# 08_INPUTCAPTURE_ENCODER.net
KiCad netlist of a schematic drawn in Altium Designer
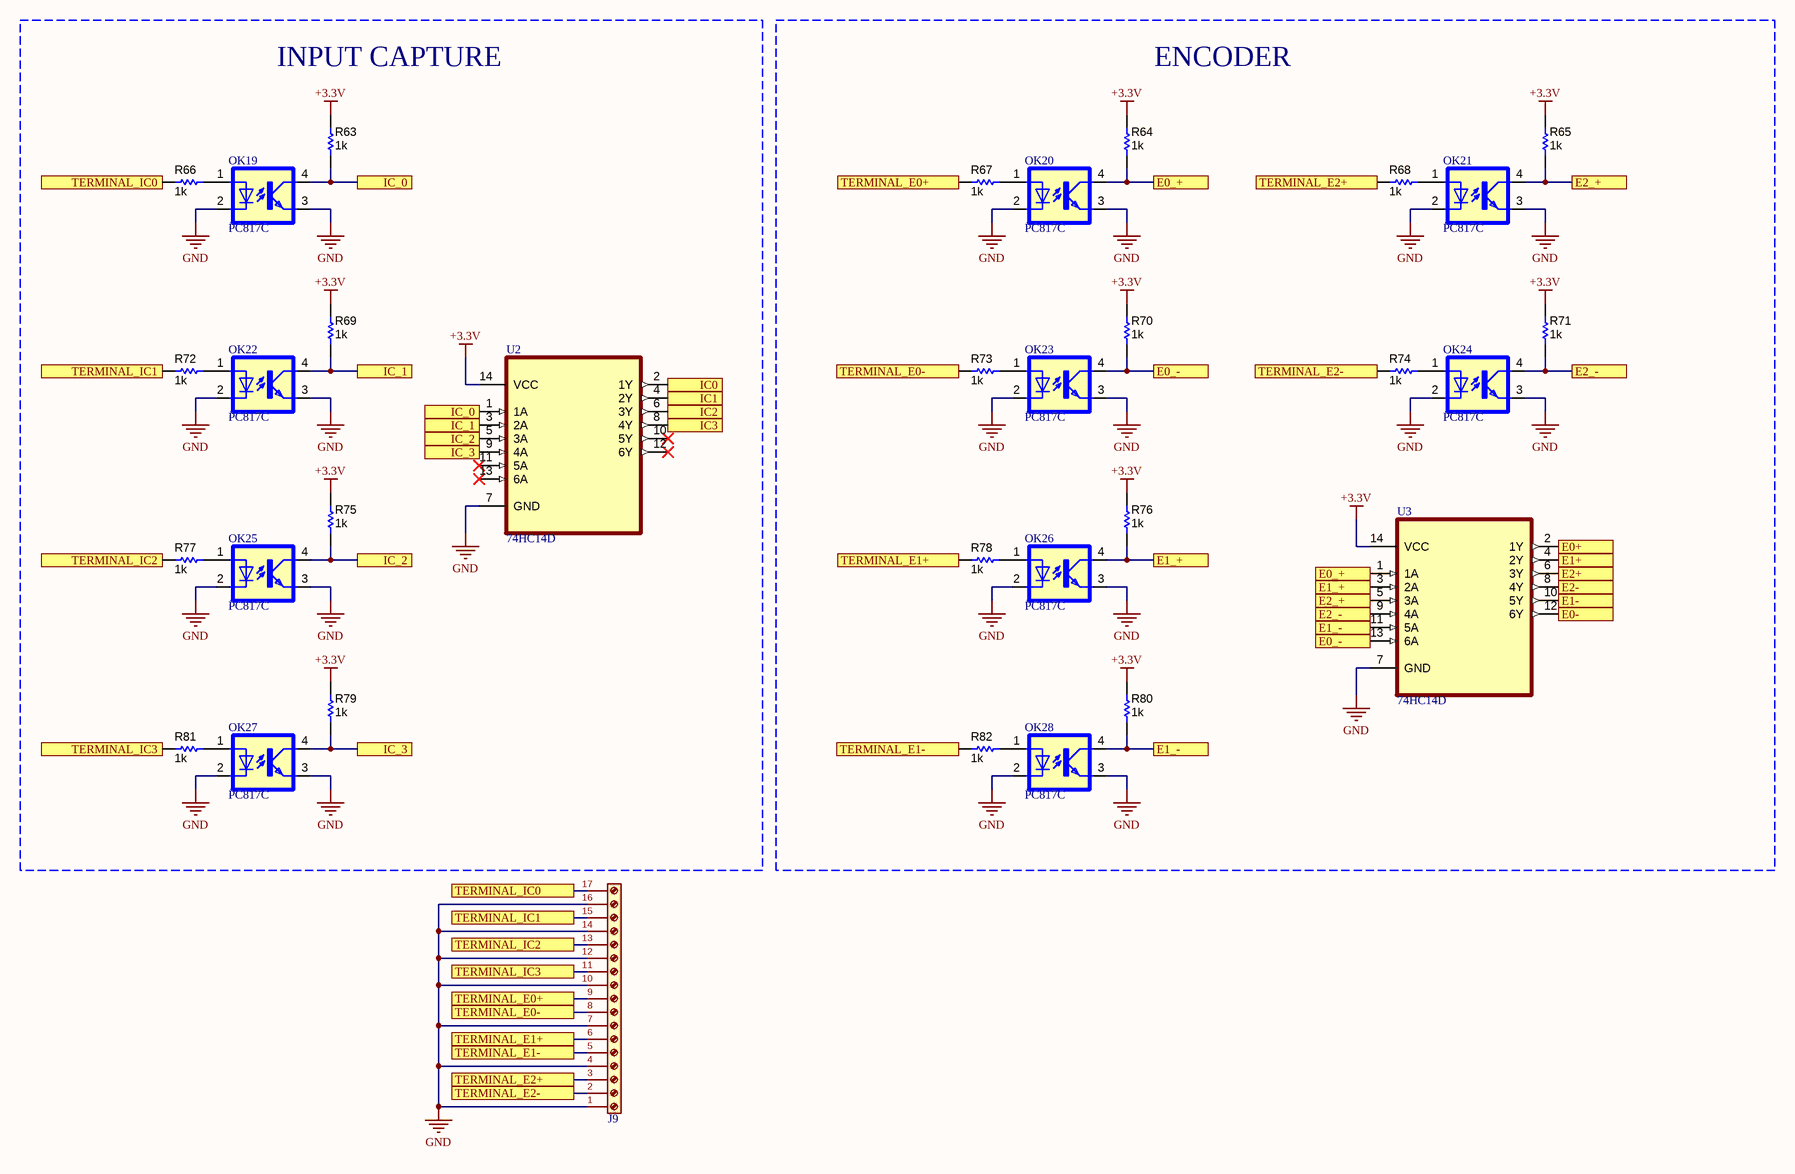
[diagram p0: 08_INPUTCAPTURE_ENCODER.SchDoc]

(export (version "E")
  (design (tool "Eeschema 10.0.6"))
  (components
    (comp (ref "J9")
      (value "Terminal_01x17_P5.00")
      (footprint "TerminalBlock_Phoenix_PT-1,5-17-5.0-H_1x17_P5.00mm_Horizontal")
      (libsource (lib "PROC051C_AWR1843BOOST_RevC") (part "Terminal_01x17_P5.00"))
    )
    (comp (ref "OK19")
      (value "PC817C")
      (footprint "SOP254P975X460-4N")
      (description "RF Mixer IC Cellular, DCS, PCS, W-CDMA, WLAN Up Converter 50MHz ~ 400MHz 6-SuperMiniMold")
      (fields (field (name "MF") "Renesas Electronics America Inc") (field (name "MP") "PC817"))
      (libsource (lib "PROC051C_AWR1843BOOST_RevC") (part "PC817C"))
    )
    (comp (ref "OK20")
      (value "PC817C")
      (footprint "SOP254P975X460-4N")
      (description "RF Mixer IC Cellular, DCS, PCS, W-CDMA, WLAN Up Converter 50MHz ~ 400MHz 6-SuperMiniMold")
      (fields (field (name "MF") "Renesas Electronics America Inc") (field (name "MP") "PC817"))
      (libsource (lib "PROC051C_AWR1843BOOST_RevC") (part "PC817C"))
    )
    (comp (ref "OK21")
      (value "PC817C")
      (footprint "SOP254P975X460-4N")
      (description "RF Mixer IC Cellular, DCS, PCS, W-CDMA, WLAN Up Converter 50MHz ~ 400MHz 6-SuperMiniMold")
      (fields (field (name "MF") "Renesas Electronics America Inc") (field (name "MP") "PC817"))
      (libsource (lib "PROC051C_AWR1843BOOST_RevC") (part "PC817C"))
    )
    (comp (ref "OK22")
      (value "PC817C")
      (footprint "SOP254P975X460-4N")
      (description "RF Mixer IC Cellular, DCS, PCS, W-CDMA, WLAN Up Converter 50MHz ~ 400MHz 6-SuperMiniMold")
      (fields (field (name "MF") "Renesas Electronics America Inc") (field (name "MP") "PC817"))
      (libsource (lib "PROC051C_AWR1843BOOST_RevC") (part "PC817C"))
    )
    (comp (ref "OK23")
      (value "PC817C")
      (footprint "SOP254P975X460-4N")
      (description "RF Mixer IC Cellular, DCS, PCS, W-CDMA, WLAN Up Converter 50MHz ~ 400MHz 6-SuperMiniMold")
      (fields (field (name "MF") "Renesas Electronics America Inc") (field (name "MP") "PC817"))
      (libsource (lib "PROC051C_AWR1843BOOST_RevC") (part "PC817C"))
    )
    (comp (ref "OK24")
      (value "PC817C")
      (footprint "SOP254P975X460-4N")
      (description "RF Mixer IC Cellular, DCS, PCS, W-CDMA, WLAN Up Converter 50MHz ~ 400MHz 6-SuperMiniMold")
      (fields (field (name "MF") "Renesas Electronics America Inc") (field (name "MP") "PC817"))
      (libsource (lib "PROC051C_AWR1843BOOST_RevC") (part "PC817C"))
    )
    (comp (ref "OK25")
      (value "PC817C")
      (footprint "SOP254P975X460-4N")
      (description "RF Mixer IC Cellular, DCS, PCS, W-CDMA, WLAN Up Converter 50MHz ~ 400MHz 6-SuperMiniMold")
      (fields (field (name "MF") "Renesas Electronics America Inc") (field (name "MP") "PC817"))
      (libsource (lib "PROC051C_AWR1843BOOST_RevC") (part "PC817C"))
    )
    (comp (ref "OK26")
      (value "PC817C")
      (footprint "SOP254P975X460-4N")
      (description "RF Mixer IC Cellular, DCS, PCS, W-CDMA, WLAN Up Converter 50MHz ~ 400MHz 6-SuperMiniMold")
      (fields (field (name "MF") "Renesas Electronics America Inc") (field (name "MP") "PC817"))
      (libsource (lib "PROC051C_AWR1843BOOST_RevC") (part "PC817C"))
    )
    (comp (ref "OK27")
      (value "PC817C")
      (footprint "SOP254P975X460-4N")
      (description "RF Mixer IC Cellular, DCS, PCS, W-CDMA, WLAN Up Converter 50MHz ~ 400MHz 6-SuperMiniMold")
      (fields (field (name "MF") "Renesas Electronics America Inc") (field (name "MP") "PC817"))
      (libsource (lib "PROC051C_AWR1843BOOST_RevC") (part "PC817C"))
    )
    (comp (ref "OK28")
      (value "PC817C")
      (footprint "SOP254P975X460-4N")
      (description "RF Mixer IC Cellular, DCS, PCS, W-CDMA, WLAN Up Converter 50MHz ~ 400MHz 6-SuperMiniMold")
      (fields (field (name "MF") "Renesas Electronics America Inc") (field (name "MP") "PC817"))
      (libsource (lib "PROC051C_AWR1843BOOST_RevC") (part "PC817C"))
    )
    (comp (ref "R63")
      (value "MCT06030Z0000ZP500")
      (footprint "0603")
      (description "RES, 0, 5%, 0.125 W, 0603")
      (fields
        (field (name "MANUFACTURER") "Vishay/Beyschlag")
        (field (name "VALUEDISPLAYED") "1k")
        (field (name "PUBLISHER") "Texas Instruments")
      )
      (libsource (lib "PROC051C_AWR1843BOOST_RevC") (part "RES 0R 0603"))
    )
    (comp (ref "R64")
      (value "MCT06030Z0000ZP500")
      (footprint "0603")
      (description "RES, 0, 5%, 0.125 W, 0603")
      (fields
        (field (name "MANUFACTURER") "Vishay/Beyschlag")
        (field (name "VALUEDISPLAYED") "1k")
        (field (name "PUBLISHER") "Texas Instruments")
      )
      (libsource (lib "PROC051C_AWR1843BOOST_RevC") (part "RES 0R 0603"))
    )
    (comp (ref "R65")
      (value "MCT06030Z0000ZP500")
      (footprint "0603")
      (description "RES, 0, 5%, 0.125 W, 0603")
      (fields
        (field (name "MANUFACTURER") "Vishay/Beyschlag")
        (field (name "VALUEDISPLAYED") "1k")
        (field (name "PUBLISHER") "Texas Instruments")
      )
      (libsource (lib "PROC051C_AWR1843BOOST_RevC") (part "RES 0R 0603"))
    )
    (comp (ref "R66")
      (value "MCT06030Z0000ZP500")
      (footprint "0603")
      (description "RES, 0, 5%, 0.125 W, 0603")
      (fields
        (field (name "MANUFACTURER") "Vishay/Beyschlag")
        (field (name "VALUEDISPLAYED") "1k")
        (field (name "PUBLISHER") "Texas Instruments")
      )
      (libsource (lib "PROC051C_AWR1843BOOST_RevC") (part "RES 0R 0603"))
    )
    (comp (ref "R67")
      (value "MCT06030Z0000ZP500")
      (footprint "0603")
      (description "RES, 0, 5%, 0.125 W, 0603")
      (fields
        (field (name "MANUFACTURER") "Vishay/Beyschlag")
        (field (name "VALUEDISPLAYED") "1k")
        (field (name "PUBLISHER") "Texas Instruments")
      )
      (libsource (lib "PROC051C_AWR1843BOOST_RevC") (part "RES 0R 0603"))
    )
    (comp (ref "R68")
      (value "MCT06030Z0000ZP500")
      (footprint "0603")
      (description "RES, 0, 5%, 0.125 W, 0603")
      (fields
        (field (name "MANUFACTURER") "Vishay/Beyschlag")
        (field (name "VALUEDISPLAYED") "1k")
        (field (name "PUBLISHER") "Texas Instruments")
      )
      (libsource (lib "PROC051C_AWR1843BOOST_RevC") (part "RES 0R 0603"))
    )
    (comp (ref "R69")
      (value "MCT06030Z0000ZP500")
      (footprint "0603")
      (description "RES, 0, 5%, 0.125 W, 0603")
      (fields
        (field (name "MANUFACTURER") "Vishay/Beyschlag")
        (field (name "VALUEDISPLAYED") "1k")
        (field (name "PUBLISHER") "Texas Instruments")
      )
      (libsource (lib "PROC051C_AWR1843BOOST_RevC") (part "RES 0R 0603"))
    )
    (comp (ref "R70")
      (value "MCT06030Z0000ZP500")
      (footprint "0603")
      (description "RES, 0, 5%, 0.125 W, 0603")
      (fields
        (field (name "MANUFACTURER") "Vishay/Beyschlag")
        (field (name "VALUEDISPLAYED") "1k")
        (field (name "PUBLISHER") "Texas Instruments")
      )
      (libsource (lib "PROC051C_AWR1843BOOST_RevC") (part "RES 0R 0603"))
    )
    (comp (ref "R71")
      (value "MCT06030Z0000ZP500")
      (footprint "0603")
      (description "RES, 0, 5%, 0.125 W, 0603")
      (fields
        (field (name "MANUFACTURER") "Vishay/Beyschlag")
        (field (name "VALUEDISPLAYED") "1k")
        (field (name "PUBLISHER") "Texas Instruments")
      )
      (libsource (lib "PROC051C_AWR1843BOOST_RevC") (part "RES 0R 0603"))
    )
    (comp (ref "R72")
      (value "MCT06030Z0000ZP500")
      (footprint "0603")
      (description "RES, 0, 5%, 0.125 W, 0603")
      (fields
        (field (name "MANUFACTURER") "Vishay/Beyschlag")
        (field (name "VALUEDISPLAYED") "1k")
        (field (name "PUBLISHER") "Texas Instruments")
      )
      (libsource (lib "PROC051C_AWR1843BOOST_RevC") (part "RES 0R 0603"))
    )
    (comp (ref "R73")
      (value "MCT06030Z0000ZP500")
      (footprint "0603")
      (description "RES, 0, 5%, 0.125 W, 0603")
      (fields
        (field (name "MANUFACTURER") "Vishay/Beyschlag")
        (field (name "VALUEDISPLAYED") "1k")
        (field (name "PUBLISHER") "Texas Instruments")
      )
      (libsource (lib "PROC051C_AWR1843BOOST_RevC") (part "RES 0R 0603"))
    )
    (comp (ref "R74")
      (value "MCT06030Z0000ZP500")
      (footprint "0603")
      (description "RES, 0, 5%, 0.125 W, 0603")
      (fields
        (field (name "MANUFACTURER") "Vishay/Beyschlag")
        (field (name "VALUEDISPLAYED") "1k")
        (field (name "PUBLISHER") "Texas Instruments")
      )
      (libsource (lib "PROC051C_AWR1843BOOST_RevC") (part "RES 0R 0603"))
    )
    (comp (ref "R75")
      (value "MCT06030Z0000ZP500")
      (footprint "0603")
      (description "RES, 0, 5%, 0.125 W, 0603")
      (fields
        (field (name "MANUFACTURER") "Vishay/Beyschlag")
        (field (name "VALUEDISPLAYED") "1k")
        (field (name "PUBLISHER") "Texas Instruments")
      )
      (libsource (lib "PROC051C_AWR1843BOOST_RevC") (part "RES 0R 0603"))
    )
    (comp (ref "R76")
      (value "MCT06030Z0000ZP500")
      (footprint "0603")
      (description "RES, 0, 5%, 0.125 W, 0603")
      (fields
        (field (name "MANUFACTURER") "Vishay/Beyschlag")
        (field (name "VALUEDISPLAYED") "1k")
        (field (name "PUBLISHER") "Texas Instruments")
      )
      (libsource (lib "PROC051C_AWR1843BOOST_RevC") (part "RES 0R 0603"))
    )
    (comp (ref "R77")
      (value "MCT06030Z0000ZP500")
      (footprint "0603")
      (description "RES, 0, 5%, 0.125 W, 0603")
      (fields
        (field (name "MANUFACTURER") "Vishay/Beyschlag")
        (field (name "VALUEDISPLAYED") "1k")
        (field (name "PUBLISHER") "Texas Instruments")
      )
      (libsource (lib "PROC051C_AWR1843BOOST_RevC") (part "RES 0R 0603"))
    )
    (comp (ref "R78")
      (value "MCT06030Z0000ZP500")
      (footprint "0603")
      (description "RES, 0, 5%, 0.125 W, 0603")
      (fields
        (field (name "MANUFACTURER") "Vishay/Beyschlag")
        (field (name "VALUEDISPLAYED") "1k")
        (field (name "PUBLISHER") "Texas Instruments")
      )
      (libsource (lib "PROC051C_AWR1843BOOST_RevC") (part "RES 0R 0603"))
    )
    (comp (ref "R79")
      (value "MCT06030Z0000ZP500")
      (footprint "0603")
      (description "RES, 0, 5%, 0.125 W, 0603")
      (fields
        (field (name "MANUFACTURER") "Vishay/Beyschlag")
        (field (name "VALUEDISPLAYED") "1k")
        (field (name "PUBLISHER") "Texas Instruments")
      )
      (libsource (lib "PROC051C_AWR1843BOOST_RevC") (part "RES 0R 0603"))
    )
    (comp (ref "R80")
      (value "MCT06030Z0000ZP500")
      (footprint "0603")
      (description "RES, 0, 5%, 0.125 W, 0603")
      (fields
        (field (name "MANUFACTURER") "Vishay/Beyschlag")
        (field (name "VALUEDISPLAYED") "1k")
        (field (name "PUBLISHER") "Texas Instruments")
      )
      (libsource (lib "PROC051C_AWR1843BOOST_RevC") (part "RES 0R 0603"))
    )
    (comp (ref "R81")
      (value "MCT06030Z0000ZP500")
      (footprint "0603")
      (description "RES, 0, 5%, 0.125 W, 0603")
      (fields
        (field (name "MANUFACTURER") "Vishay/Beyschlag")
        (field (name "VALUEDISPLAYED") "1k")
        (field (name "PUBLISHER") "Texas Instruments")
      )
      (libsource (lib "PROC051C_AWR1843BOOST_RevC") (part "RES 0R 0603"))
    )
    (comp (ref "R82")
      (value "MCT06030Z0000ZP500")
      (footprint "0603")
      (description "RES, 0, 5%, 0.125 W, 0603")
      (fields
        (field (name "MANUFACTURER") "Vishay/Beyschlag")
        (field (name "VALUEDISPLAYED") "1k")
        (field (name "PUBLISHER") "Texas Instruments")
      )
      (libsource (lib "PROC051C_AWR1843BOOST_RevC") (part "RES 0R 0603"))
    )
    (comp (ref "U2")
      (value "74HC14D")
      (footprint "SOIC127P600X175-14N")
      (description "Inverter IC 6 Channel Schmitt Trigger 14-SOIC")
      (fields (field (name "MF") "Toshiba"))
      (libsource (lib "PROC051C_AWR1843BOOST_RevC") (part "74HC14D"))
    )
    (comp (ref "U3")
      (value "74HC14D")
      (footprint "SOIC127P600X175-14N")
      (description "Inverter IC 6 Channel Schmitt Trigger 14-SOIC")
      (fields (field (name "MF") "Toshiba"))
      (libsource (lib "PROC051C_AWR1843BOOST_RevC") (part "74HC14D"))
    )
  )
  (nets
    (net (code "1") (name "+3.3V") (class "Default")
      (node (ref "R63") (pin "2") (pinfunction "2_2") (pintype "passive"))
      (node (ref "R64") (pin "2") (pinfunction "2_2") (pintype "passive"))
      (node (ref "R65") (pin "2") (pinfunction "2_2") (pintype "passive"))
      (node (ref "R69") (pin "2") (pinfunction "2_2") (pintype "passive"))
      (node (ref "R70") (pin "2") (pinfunction "2_2") (pintype "passive"))
      (node (ref "R71") (pin "2") (pinfunction "2_2") (pintype "passive"))
      (node (ref "R75") (pin "2") (pinfunction "2_2") (pintype "passive"))
      (node (ref "R76") (pin "2") (pinfunction "2_2") (pintype "passive"))
      (node (ref "R79") (pin "2") (pinfunction "2_2") (pintype "passive"))
      (node (ref "R80") (pin "2") (pinfunction "2_2") (pintype "passive"))
      (node (ref "U2") (pin "14") (pinfunction "VCC_14") (pintype "power_in"))
      (node (ref "U3") (pin "14") (pinfunction "VCC_14") (pintype "power_in"))
    )
    (net (code "2") (name "/E0+") (class "Default")
      (node (ref "U3") (pin "2") (pinfunction "1Y_2") (pintype "output"))
    )
    (net (code "3") (name "/E0-") (class "Default")
      (node (ref "U3") (pin "12") (pinfunction "6Y_12") (pintype "output"))
    )
    (net (code "4") (name "/E0_+") (class "Default")
      (node (ref "OK20") (pin "4") (pinfunction "COL_4") (pintype "passive"))
      (node (ref "R64") (pin "1") (pinfunction "1_1") (pintype "passive"))
      (node (ref "U3") (pin "1") (pinfunction "1A_1") (pintype "input"))
    )
    (net (code "5") (name "/E0_-") (class "Default")
      (node (ref "OK23") (pin "4") (pinfunction "COL_4") (pintype "passive"))
      (node (ref "R70") (pin "1") (pinfunction "1_1") (pintype "passive"))
      (node (ref "U3") (pin "13") (pinfunction "6A_13") (pintype "input"))
    )
    (net (code "6") (name "/E1+") (class "Default")
      (node (ref "U3") (pin "4") (pinfunction "2Y_4") (pintype "output"))
    )
    (net (code "7") (name "/E1-") (class "Default")
      (node (ref "U3") (pin "10") (pinfunction "5Y_10") (pintype "output"))
    )
    (net (code "8") (name "/E1_+") (class "Default")
      (node (ref "OK26") (pin "4") (pinfunction "COL_4") (pintype "passive"))
      (node (ref "R76") (pin "1") (pinfunction "1_1") (pintype "passive"))
      (node (ref "U3") (pin "3") (pinfunction "2A_3") (pintype "input"))
    )
    (net (code "9") (name "/E1_-") (class "Default")
      (node (ref "OK28") (pin "4") (pinfunction "COL_4") (pintype "passive"))
      (node (ref "R80") (pin "1") (pinfunction "1_1") (pintype "passive"))
      (node (ref "U3") (pin "11") (pinfunction "5A_11") (pintype "input"))
    )
    (net (code "10") (name "/E2+") (class "Default")
      (node (ref "U3") (pin "6") (pinfunction "3Y_6") (pintype "output"))
    )
    (net (code "11") (name "/E2-") (class "Default")
      (node (ref "U3") (pin "8") (pinfunction "4Y_8") (pintype "output"))
    )
    (net (code "12") (name "/E2_+") (class "Default")
      (node (ref "OK21") (pin "4") (pinfunction "COL_4") (pintype "passive"))
      (node (ref "R65") (pin "1") (pinfunction "1_1") (pintype "passive"))
      (node (ref "U3") (pin "5") (pinfunction "3A_5") (pintype "input"))
    )
    (net (code "13") (name "/E2_-") (class "Default")
      (node (ref "OK24") (pin "4") (pinfunction "COL_4") (pintype "passive"))
      (node (ref "R71") (pin "1") (pinfunction "1_1") (pintype "passive"))
      (node (ref "U3") (pin "9") (pinfunction "4A_9") (pintype "input"))
    )
    (net (code "14") (name "/IC0") (class "Default")
      (node (ref "U2") (pin "2") (pinfunction "1Y_2") (pintype "output"))
    )
    (net (code "15") (name "/IC1") (class "Default")
      (node (ref "U2") (pin "4") (pinfunction "2Y_4") (pintype "output"))
    )
    (net (code "16") (name "/IC2") (class "Default")
      (node (ref "U2") (pin "6") (pinfunction "3Y_6") (pintype "output"))
    )
    (net (code "17") (name "/IC3") (class "Default")
      (node (ref "U2") (pin "8") (pinfunction "4Y_8") (pintype "output"))
    )
    (net (code "18") (name "/IC_0") (class "Default")
      (node (ref "OK19") (pin "4") (pinfunction "COL_4") (pintype "passive"))
      (node (ref "R63") (pin "1") (pinfunction "1_1") (pintype "passive"))
      (node (ref "U2") (pin "1") (pinfunction "1A_1") (pintype "input"))
    )
    (net (code "19") (name "/IC_1") (class "Default")
      (node (ref "OK22") (pin "4") (pinfunction "COL_4") (pintype "passive"))
      (node (ref "R69") (pin "1") (pinfunction "1_1") (pintype "passive"))
      (node (ref "U2") (pin "3") (pinfunction "2A_3") (pintype "input"))
    )
    (net (code "20") (name "/IC_2") (class "Default")
      (node (ref "OK25") (pin "4") (pinfunction "COL_4") (pintype "passive"))
      (node (ref "R75") (pin "1") (pinfunction "1_1") (pintype "passive"))
      (node (ref "U2") (pin "5") (pinfunction "3A_5") (pintype "input"))
    )
    (net (code "21") (name "/IC_3") (class "Default")
      (node (ref "OK27") (pin "4") (pinfunction "COL_4") (pintype "passive"))
      (node (ref "R79") (pin "1") (pinfunction "1_1") (pintype "passive"))
      (node (ref "U2") (pin "9") (pinfunction "4A_9") (pintype "input"))
    )
    (net (code "22") (name "/TERMINAL_E0+") (class "Default")
      (node (ref "J9") (pin "9") (pinfunction "Pin_9_9") (pintype "passive"))
      (node (ref "R67") (pin "1") (pinfunction "1_1") (pintype "passive"))
    )
    (net (code "23") (name "/TERMINAL_E0-") (class "Default")
      (node (ref "J9") (pin "8") (pinfunction "Pin_8_8") (pintype "passive"))
      (node (ref "R73") (pin "1") (pinfunction "1_1") (pintype "passive"))
    )
    (net (code "24") (name "/TERMINAL_E1+") (class "Default")
      (node (ref "J9") (pin "6") (pinfunction "Pin_6_6") (pintype "passive"))
      (node (ref "R78") (pin "1") (pinfunction "1_1") (pintype "passive"))
    )
    (net (code "25") (name "/TERMINAL_E1-") (class "Default")
      (node (ref "J9") (pin "5") (pinfunction "Pin_5_5") (pintype "passive"))
      (node (ref "R82") (pin "1") (pinfunction "1_1") (pintype "passive"))
    )
    (net (code "26") (name "/TERMINAL_E2+") (class "Default")
      (node (ref "J9") (pin "3") (pinfunction "Pin_3_3") (pintype "passive"))
      (node (ref "R68") (pin "1") (pinfunction "1_1") (pintype "passive"))
    )
    (net (code "27") (name "/TERMINAL_E2-") (class "Default")
      (node (ref "J9") (pin "2") (pinfunction "Pin_2_2") (pintype "passive"))
      (node (ref "R74") (pin "1") (pinfunction "1_1") (pintype "passive"))
    )
    (net (code "28") (name "/TERMINAL_IC0") (class "Default")
      (node (ref "J9") (pin "17") (pinfunction "Pin_17_17") (pintype "passive"))
      (node (ref "R66") (pin "1") (pinfunction "1_1") (pintype "passive"))
    )
    (net (code "29") (name "/TERMINAL_IC1") (class "Default")
      (node (ref "J9") (pin "15") (pinfunction "Pin_15_15") (pintype "passive"))
      (node (ref "R72") (pin "1") (pinfunction "1_1") (pintype "passive"))
    )
    (net (code "30") (name "/TERMINAL_IC2") (class "Default")
      (node (ref "J9") (pin "13") (pinfunction "Pin_13_13") (pintype "passive"))
      (node (ref "R77") (pin "1") (pinfunction "1_1") (pintype "passive"))
    )
    (net (code "31") (name "/TERMINAL_IC3") (class "Default")
      (node (ref "J9") (pin "11") (pinfunction "Pin_11_11") (pintype "passive"))
      (node (ref "R81") (pin "1") (pinfunction "1_1") (pintype "passive"))
    )
    (net (code "32") (name "GND") (class "Default")
      (node (ref "J9") (pin "1") (pinfunction "Pin_1_1") (pintype "passive"))
      (node (ref "J9") (pin "10") (pinfunction "Pin_10_10") (pintype "passive"))
      (node (ref "J9") (pin "12") (pinfunction "Pin_12_12") (pintype "passive"))
      (node (ref "J9") (pin "14") (pinfunction "Pin_14_14") (pintype "passive"))
      (node (ref "J9") (pin "16") (pinfunction "Pin_16_16") (pintype "passive"))
      (node (ref "J9") (pin "4") (pinfunction "Pin_4_4") (pintype "passive"))
      (node (ref "J9") (pin "7") (pinfunction "Pin_7_7") (pintype "passive"))
      (node (ref "OK19") (pin "2") (pinfunction "C_2") (pintype "passive"))
      (node (ref "OK19") (pin "3") (pinfunction "EMIT_3") (pintype "passive"))
      (node (ref "OK20") (pin "2") (pinfunction "C_2") (pintype "passive"))
      (node (ref "OK20") (pin "3") (pinfunction "EMIT_3") (pintype "passive"))
      (node (ref "OK21") (pin "2") (pinfunction "C_2") (pintype "passive"))
      (node (ref "OK21") (pin "3") (pinfunction "EMIT_3") (pintype "passive"))
      (node (ref "OK22") (pin "2") (pinfunction "C_2") (pintype "passive"))
      (node (ref "OK22") (pin "3") (pinfunction "EMIT_3") (pintype "passive"))
      (node (ref "OK23") (pin "2") (pinfunction "C_2") (pintype "passive"))
      (node (ref "OK23") (pin "3") (pinfunction "EMIT_3") (pintype "passive"))
      (node (ref "OK24") (pin "2") (pinfunction "C_2") (pintype "passive"))
      (node (ref "OK24") (pin "3") (pinfunction "EMIT_3") (pintype "passive"))
      (node (ref "OK25") (pin "2") (pinfunction "C_2") (pintype "passive"))
      (node (ref "OK25") (pin "3") (pinfunction "EMIT_3") (pintype "passive"))
      (node (ref "OK26") (pin "2") (pinfunction "C_2") (pintype "passive"))
      (node (ref "OK26") (pin "3") (pinfunction "EMIT_3") (pintype "passive"))
      (node (ref "OK27") (pin "2") (pinfunction "C_2") (pintype "passive"))
      (node (ref "OK27") (pin "3") (pinfunction "EMIT_3") (pintype "passive"))
      (node (ref "OK28") (pin "2") (pinfunction "C_2") (pintype "passive"))
      (node (ref "OK28") (pin "3") (pinfunction "EMIT_3") (pintype "passive"))
      (node (ref "U2") (pin "7") (pinfunction "GND_7") (pintype "passive"))
      (node (ref "U3") (pin "7") (pinfunction "GND_7") (pintype "passive"))
    )
    (net (code "33") (name "Net-(OK19-A)") (class "Default")
      (node (ref "OK19") (pin "1") (pinfunction "A_1") (pintype "passive"))
      (node (ref "R66") (pin "2") (pinfunction "2_2") (pintype "passive"))
    )
    (net (code "34") (name "Net-(OK20-A)") (class "Default")
      (node (ref "OK20") (pin "1") (pinfunction "A_1") (pintype "passive"))
      (node (ref "R67") (pin "2") (pinfunction "2_2") (pintype "passive"))
    )
    (net (code "35") (name "Net-(OK21-A)") (class "Default")
      (node (ref "OK21") (pin "1") (pinfunction "A_1") (pintype "passive"))
      (node (ref "R68") (pin "2") (pinfunction "2_2") (pintype "passive"))
    )
    (net (code "36") (name "Net-(OK22-A)") (class "Default")
      (node (ref "OK22") (pin "1") (pinfunction "A_1") (pintype "passive"))
      (node (ref "R72") (pin "2") (pinfunction "2_2") (pintype "passive"))
    )
    (net (code "37") (name "Net-(OK23-A)") (class "Default")
      (node (ref "OK23") (pin "1") (pinfunction "A_1") (pintype "passive"))
      (node (ref "R73") (pin "2") (pinfunction "2_2") (pintype "passive"))
    )
    (net (code "38") (name "Net-(OK24-A)") (class "Default")
      (node (ref "OK24") (pin "1") (pinfunction "A_1") (pintype "passive"))
      (node (ref "R74") (pin "2") (pinfunction "2_2") (pintype "passive"))
    )
    (net (code "39") (name "Net-(OK25-A)") (class "Default")
      (node (ref "OK25") (pin "1") (pinfunction "A_1") (pintype "passive"))
      (node (ref "R77") (pin "2") (pinfunction "2_2") (pintype "passive"))
    )
    (net (code "40") (name "Net-(OK26-A)") (class "Default")
      (node (ref "OK26") (pin "1") (pinfunction "A_1") (pintype "passive"))
      (node (ref "R78") (pin "2") (pinfunction "2_2") (pintype "passive"))
    )
    (net (code "41") (name "Net-(OK27-A)") (class "Default")
      (node (ref "OK27") (pin "1") (pinfunction "A_1") (pintype "passive"))
      (node (ref "R81") (pin "2") (pinfunction "2_2") (pintype "passive"))
    )
    (net (code "42") (name "Net-(OK28-A)") (class "Default")
      (node (ref "OK28") (pin "1") (pinfunction "A_1") (pintype "passive"))
      (node (ref "R82") (pin "2") (pinfunction "2_2") (pintype "passive"))
    )
    (net (code "43") (name "unconnected-(U2-5A-Pad11)") (class "Default")
      (node (ref "U2") (pin "11") (pinfunction "5A_11") (pintype "input+no_connect"))
    )
    (net (code "44") (name "unconnected-(U2-5Y-Pad10)") (class "Default")
      (node (ref "U2") (pin "10") (pinfunction "5Y_10") (pintype "output+no_connect"))
    )
    (net (code "45") (name "unconnected-(U2-6A-Pad13)") (class "Default")
      (node (ref "U2") (pin "13") (pinfunction "6A_13") (pintype "input+no_connect"))
    )
    (net (code "46") (name "unconnected-(U2-6Y-Pad12)") (class "Default")
      (node (ref "U2") (pin "12") (pinfunction "6Y_12") (pintype "output+no_connect"))
    )
  )
)
